# AUAV-X1_POWER_R1.net
KiCad netlist of a schematic drawn in Altium Designer
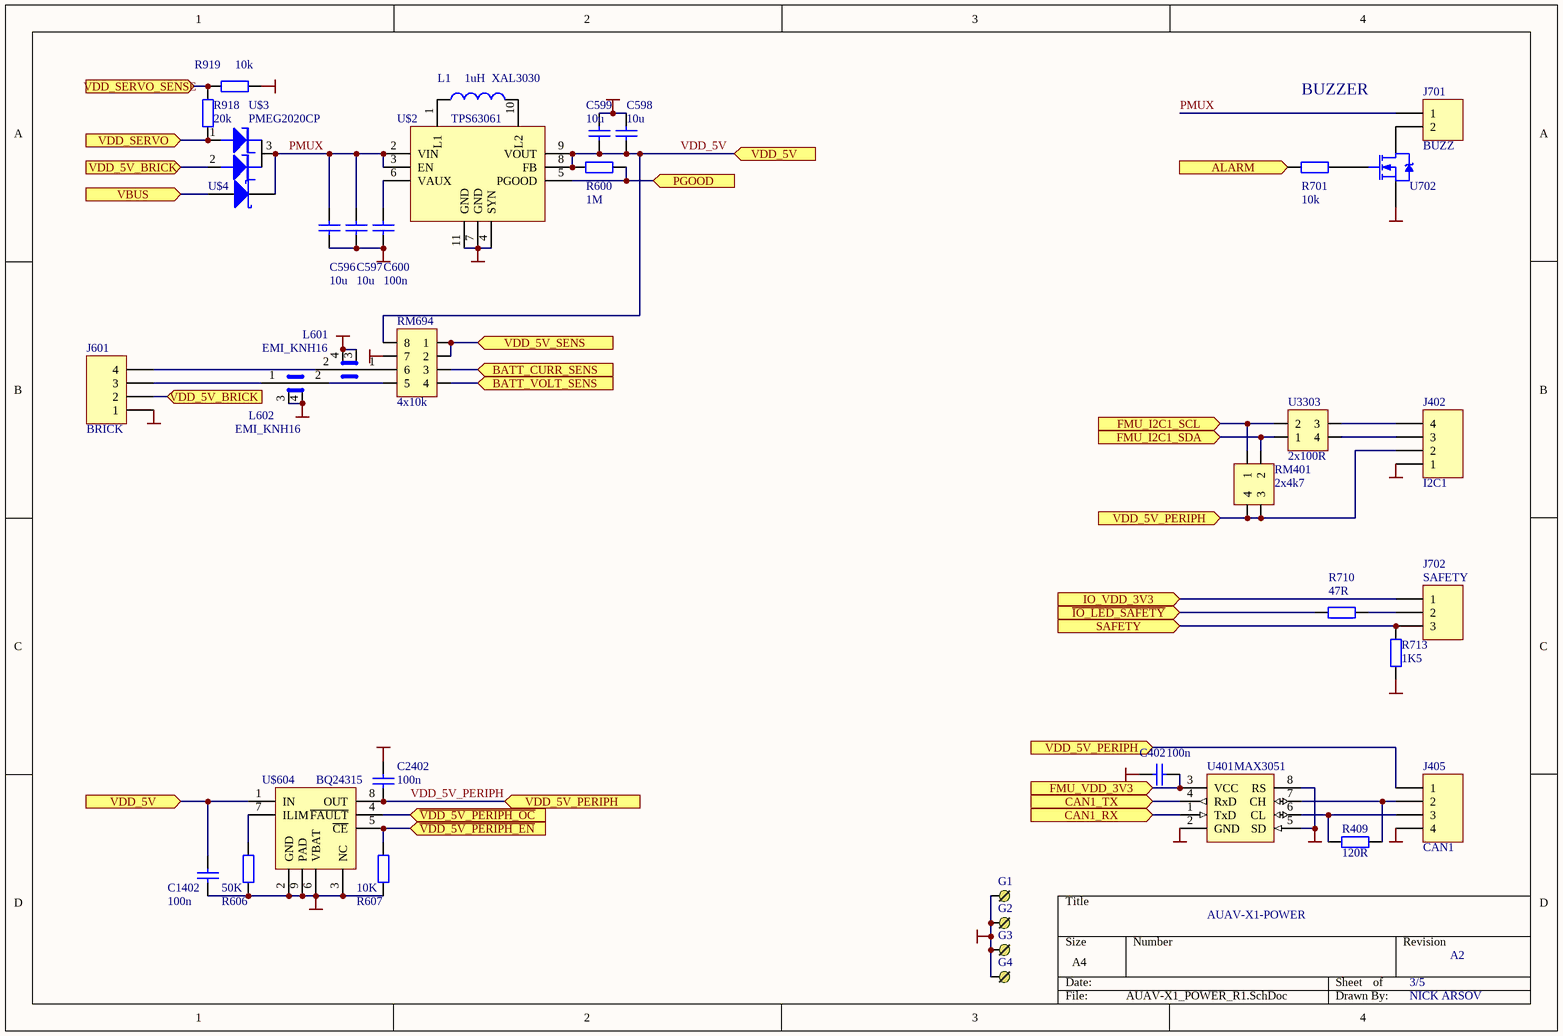
[diagram p0: AUAV-X1_POWER_R1.SchDoc]

(export (version "E")
  (design (tool "Eeschema 10.0.6"))
  (components
    (comp (ref "C402")
      (value "100n")
      (footprint "0402A")
      (description "Capacitor")
      (fields (field (name "PUBLISHER") "Altium Limited"))
      (libsource (lib "Miscellaneous Devices") (part "Cap"))
    )
    (comp (ref "C596")
      (value "10u")
      (footprint "0805A")
      (description "Capacitor")
      (fields (field (name "PUBLISHER") "Altium Limited"))
      (libsource (lib "Miscellaneous Devices") (part "Cap"))
    )
    (comp (ref "C597")
      (value "10u")
      (footprint "0805A")
      (description "Capacitor")
      (fields (field (name "PUBLISHER") "Altium Limited"))
      (libsource (lib "Miscellaneous Devices") (part "Cap"))
    )
    (comp (ref "C598")
      (value "10u")
      (footprint "0805A")
      (description "Capacitor")
      (fields (field (name "PUBLISHER") "Altium Limited"))
      (libsource (lib "Miscellaneous Devices") (part "Cap"))
    )
    (comp (ref "C599")
      (value "10u")
      (footprint "0805A")
      (description "Capacitor")
      (fields (field (name "PUBLISHER") "Altium Limited"))
      (libsource (lib "Miscellaneous Devices") (part "Cap"))
    )
    (comp (ref "C600")
      (value "100n")
      (footprint "0402A")
      (description "Capacitor")
      (fields (field (name "PUBLISHER") "Altium Limited"))
      (libsource (lib "Miscellaneous Devices") (part "Cap"))
    )
    (comp (ref "C1402")
      (value "100n")
      (footprint "0402A")
      (description "Capacitor")
      (fields (field (name "PUBLISHER") "Altium Limited"))
      (libsource (lib "Miscellaneous Devices") (part "Cap"))
    )
    (comp (ref "C2402")
      (value "100n")
      (footprint "0402A")
      (description "Capacitor")
      (fields (field (name "PUBLISHER") "Altium Limited"))
      (libsource (lib "Miscellaneous Devices") (part "Cap"))
    )
    (comp (ref "G1") (value "PLUG") (footprint "SMT_PAD_ROUND") (libsource (lib "My_Altium") (part "PLUG")))
    (comp (ref "G2") (value "PLUG") (footprint "SMT_PAD_ROUND") (libsource (lib "My_Altium") (part "PLUG")))
    (comp (ref "G3") (value "PLUG") (footprint "SMT_PAD_ROUND") (libsource (lib "My_Altium") (part "PLUG")))
    (comp (ref "G4") (value "PLUG") (footprint "SMT_PAD_ROUND") (libsource (lib "My_Altium") (part "PLUG")))
    (comp (ref "J402")
      (value "I2C1")
      (footprint "HDR1X4")
      (description "Header, 4-Pin")
      (fields (field (name "PUBLISHER") "Altium Limited"))
      (libsource (lib "") (part "Header 4_2"))
    )
    (comp (ref "J405")
      (value "CAN1")
      (footprint "HDR1X4")
      (description "Header, 4-Pin")
      (fields (field (name "PUBLISHER") "Altium Limited"))
      (libsource (lib "Miscellaneous Connectors") (part "Header 4"))
    )
    (comp (ref "J601")
      (value "BRICK")
      (footprint "HDR1X4")
      (description "Header, 4-Pin")
      (fields (field (name "PUBLISHER") "Altium Limited"))
      (libsource (lib "") (part "Header 4_1"))
    )
    (comp (ref "J701")
      (value "BUZZ")
      (footprint "HDR1X2")
      (description "Header, 2-Pin")
      (fields (field (name "PUBLISHER") "Altium Limited"))
      (libsource (lib "Miscellaneous Connectors") (part "Header 2"))
    )
    (comp (ref "J702")
      (value "SAFETY")
      (footprint "HDR1X3")
      (description "Header, 3-Pin")
      (fields (field (name "PUBLISHER") "Altium Limited"))
      (libsource (lib "Miscellaneous Connectors") (part "Header 3"))
    )
    (comp (ref "L1")
      (value "XAL3030")
      (footprint "XAL4040")
      (description "Inductor")
      (fields (field (name "ALTIUM_VALUE") "1uH") (field (name "PUBLISHER") "Altium Limited"))
      (libsource (lib "Miscellaneous Devices") (part "Inductor"))
    )
    (comp (ref "L601")
      (value "EMI_KNH16")
      (footprint "EMI_KNH16_0603")
      (libsource (lib "My_Altium") (part "EMI_KNH10"))
    )
    (comp (ref "L602")
      (value "EMI_KNH16")
      (footprint "EMI_KNH16_0603")
      (libsource (lib "My_Altium") (part "EMI_KNH10"))
    )
    (comp (ref "R409")
      (value "120R")
      (footprint "0603A")
      (description "Resistor")
      (fields (field (name "PUBLISHER") "Altium Limited"))
      (libsource (lib "Miscellaneous Devices") (part "Res2"))
    )
    (comp (ref "R600")
      (value "1M")
      (footprint "0402A")
      (description "Resistor")
      (fields (field (name "PUBLISHER") "Altium Limited"))
      (libsource (lib "") (part "Res2_2"))
    )
    (comp (ref "R606")
      (value "50K")
      (footprint "0402A")
      (description "Resistor")
      (fields (field (name "PUBLISHER") "Altium Limited"))
      (libsource (lib "") (part "Res2_1"))
    )
    (comp (ref "R607")
      (value "10K")
      (footprint "0402A")
      (description "Resistor")
      (fields (field (name "PUBLISHER") "Altium Limited"))
      (libsource (lib "") (part "Res2_1"))
    )
    (comp (ref "R701")
      (value "10k")
      (footprint "0402A")
      (description "Resistor")
      (fields (field (name "PUBLISHER") "Altium Limited"))
      (libsource (lib "") (part "Res2_2"))
    )
    (comp (ref "R710")
      (value "47R")
      (footprint "0402A")
      (description "Resistor")
      (fields (field (name "PUBLISHER") "Altium Limited"))
      (libsource (lib "Miscellaneous Devices") (part "Res2"))
    )
    (comp (ref "R713")
      (value "1K5")
      (footprint "0402A")
      (description "Resistor")
      (fields (field (name "PUBLISHER") "Altium Limited"))
      (libsource (lib "") (part "Res2_3"))
    )
    (comp (ref "R918")
      (value "20k")
      (footprint "0402A")
      (description "Resistor")
      (fields (field (name "PUBLISHER") "Altium Limited"))
      (libsource (lib "") (part "Res2_3"))
    )
    (comp (ref "R919")
      (value "10k")
      (footprint "0402A")
      (description "Resistor")
      (fields (field (name "PUBLISHER") "Altium Limited"))
      (libsource (lib "") (part "Res2_2"))
    )
    (comp (ref "RM401") (value "2x4k7") (footprint "RM2_0804") (libsource (lib "") (part "RES_SMD_2_1")))
    (comp (ref "RM694")
      (value "4x10k")
      (footprint "RM4_0804")
      (libsource (lib "My_Altium") (part "RES_SMD_4"))
    )
    (comp (ref "U$2")
      (value "TPS63061")
      (footprint "TPS63061")
      (libsource (lib "My_Altium") (part "TPS63061"))
    )
    (comp (ref "U$3")
      (value "PMEG2020CP")
      (footprint "pmeg2020cp")
      (libsource (lib "My_Altium") (part "PMEG2020CP"))
    )
    (comp (ref "U$4")
      (value "D Schottky")
      (footprint "SOD323F")
      (description "Schottky Diode")
      (fields (field (name "PUBLISHER") "Altium Limited"))
      (libsource (lib "Miscellaneous Devices") (part "D Schottky"))
    )
    (comp (ref "U$604")
      (value "BQ24315")
      (footprint "BQ24315")
      (libsource (lib "My_Altium") (part "BQ24315"))
    )
    (comp (ref "U401")
      (value "MAX3051")
      (footprint "SOT-23-8")
      (libsource (lib "My_Altium") (part "MAX3051"))
    )
    (comp (ref "U702")
      (value "ZXMN2F34MA")
      (footprint "2N7002-SOT323")
      (description "N-Channel Power MOSFET")
      (fields (field (name "PUBLISHER") "Altium Limited"))
      (libsource (lib "Miscellaneous Devices") (part "NMOS-2"))
    )
    (comp (ref "U3303")
      (value "2x100R")
      (footprint "RM2_0804")
      (libsource (lib "My_Altium") (part "RES_SMD_2"))
    )
  )
  (nets
    (net (code "1") (name "/ALARM") (class "Default")
      (node (ref "R701") (pin "1") (pinfunction "1_1") (pintype "passive"))
    )
    (net (code "2") (name "/BATT_CURR_SENS") (class "Default")
      (node (ref "RM694") (pin "3") (pinfunction "3_3") (pintype "passive"))
    )
    (net (code "3") (name "/BATT_VOLT_SENS") (class "Default")
      (node (ref "RM694") (pin "4") (pinfunction "4_4") (pintype "passive"))
    )
    (net (code "4") (name "/CAN1_RX") (class "Default")
      (node (ref "U401") (pin "1") (pinfunction "TxD_1") (pintype "input"))
    )
    (net (code "5") (name "/CAN1_TX") (class "Default")
      (node (ref "U401") (pin "4") (pinfunction "RxD_4") (pintype "output"))
    )
    (net (code "6") (name "/FMU_I2C1_SCL") (class "Default")
      (node (ref "RM401") (pin "1") (pinfunction "1_1") (pintype "passive"))
      (node (ref "U3303") (pin "2") (pinfunction "2_2") (pintype "passive"))
    )
    (net (code "7") (name "/FMU_I2C1_SDA") (class "Default")
      (node (ref "RM401") (pin "2") (pinfunction "2_2") (pintype "passive"))
      (node (ref "U3303") (pin "1") (pinfunction "1_1") (pintype "passive"))
    )
    (net (code "8") (name "/FMU_VDD_3V3") (class "Default")
      (node (ref "C402") (pin "2") (pinfunction "2_2") (pintype "passive"))
      (node (ref "U401") (pin "3") (pinfunction "VCC_3") (pintype "power_in"))
    )
    (net (code "9") (name "/IO_VDD_3V3") (class "Default")
      (node (ref "J702") (pin "1") (pinfunction "1_1") (pintype "passive"))
    )
    (net (code "10") (name "/PGOOD") (class "Default")
      (node (ref "R600") (pin "2") (pinfunction "2_2") (pintype "passive"))
      (node (ref "U$2") (pin "5") (pinfunction "PGOOD_5") (pintype "passive"))
    )
    (net (code "11") (name "/PMUX") (class "Default")
      (node (ref "C596") (pin "2") (pinfunction "2_2") (pintype "passive"))
      (node (ref "C597") (pin "2") (pinfunction "2_2") (pintype "passive"))
      (node (ref "J701") (pin "1") (pinfunction "1_1") (pintype "passive"))
      (node (ref "U$2") (pin "2") (pinfunction "VIN_2") (pintype "passive"))
      (node (ref "U$2") (pin "3") (pinfunction "EN_3") (pintype "passive"))
      (node (ref "U$3") (pin "3") (pintype "passive"))
      (node (ref "U$4") (pin "2") (pinfunction "K_2") (pintype "passive"))
    )
    (net (code "12") (name "/SAFETY") (class "Default")
      (node (ref "J702") (pin "3") (pinfunction "3_3") (pintype "passive"))
      (node (ref "R713") (pin "1") (pinfunction "1_1") (pintype "passive"))
    )
    (net (code "13") (name "/VBUS") (class "Default")
      (node (ref "U$4") (pin "1") (pinfunction "A_1") (pintype "passive"))
    )
    (net (code "14") (name "/VDD_5V") (class "Default")
      (node (ref "C1402") (pin "2") (pinfunction "2_2") (pintype "passive"))
      (node (ref "C598") (pin "2") (pinfunction "2_2") (pintype "passive"))
      (node (ref "C599") (pin "2") (pinfunction "2_2") (pintype "passive"))
      (node (ref "R600") (pin "1") (pinfunction "1_1") (pintype "passive"))
      (node (ref "RM694") (pin "8") (pinfunction "8_8") (pintype "passive"))
      (node (ref "U$2") (pin "8") (pinfunction "FB_8") (pintype "passive"))
      (node (ref "U$2") (pin "9") (pinfunction "VOUT_9") (pintype "passive"))
      (node (ref "U$604") (pin "1") (pinfunction "IN_1") (pintype "power_in"))
    )
    (net (code "15") (name "/VDD_5V_BRICK") (class "Default")
      (node (ref "J601") (pin "2") (pinfunction "2_2") (pintype "passive"))
      (node (ref "U$3") (pin "2") (pintype "passive"))
    )
    (net (code "16") (name "/VDD_5V_PERIPH") (class "Default")
      (node (ref "C2402") (pin "2") (pinfunction "2_2") (pintype "passive"))
      (node (ref "J402") (pin "2") (pinfunction "2_2") (pintype "passive"))
      (node (ref "J405") (pin "1") (pinfunction "1_1") (pintype "passive"))
      (node (ref "RM401") (pin "3") (pinfunction "3_3") (pintype "passive"))
      (node (ref "RM401") (pin "4") (pinfunction "4_4") (pintype "passive"))
      (node (ref "U$604") (pin "8") (pinfunction "OUT_8") (pintype "passive"))
    )
    (net (code "17") (name "/VDD_5V_SENS") (class "Default")
      (node (ref "RM694") (pin "1") (pinfunction "1_1") (pintype "passive"))
      (node (ref "RM694") (pin "2") (pinfunction "2_2") (pintype "passive"))
    )
    (net (code "18") (name "/VDD_SERVO") (class "Default")
      (node (ref "R918") (pin "2") (pinfunction "2_2") (pintype "passive"))
      (node (ref "U$3") (pin "1") (pintype "passive"))
    )
    (net (code "19") (name "/VDD_SERVO_SENSE") (class "Default")
      (node (ref "R918") (pin "1") (pinfunction "1_1") (pintype "passive"))
      (node (ref "R919") (pin "1") (pinfunction "1_1") (pintype "passive"))
    )
    (net (code "20") (name "/~{IO_LED_SAFETY}") (class "Default")
      (node (ref "R710") (pin "2") (pinfunction "2_2") (pintype "passive"))
    )
    (net (code "21") (name "/~{VDD_5V_PERIPH_EN}") (class "Default")
      (node (ref "R607") (pin "2") (pinfunction "2_2") (pintype "passive"))
      (node (ref "U$604") (pin "5") (pinfunction "~{CE}_5") (pintype "passive"))
    )
    (net (code "22") (name "/~{VDD_5V_PERIPH_OC}") (class "Default")
      (node (ref "U$604") (pin "4") (pinfunction "~{FAULT}_4") (pintype "passive"))
    )
    (net (code "23") (name "GND") (class "Default")
      (node (ref "C1402") (pin "1") (pinfunction "1_1") (pintype "passive"))
      (node (ref "C2402") (pin "1") (pinfunction "1_1") (pintype "passive"))
      (node (ref "C402") (pin "1") (pinfunction "1_1") (pintype "passive"))
      (node (ref "C596") (pin "1") (pinfunction "1_1") (pintype "passive"))
      (node (ref "C597") (pin "1") (pinfunction "1_1") (pintype "passive"))
      (node (ref "C598") (pin "1") (pinfunction "1_1") (pintype "passive"))
      (node (ref "C599") (pin "1") (pinfunction "1_1") (pintype "passive"))
      (node (ref "C600") (pin "1") (pinfunction "1_1") (pintype "passive"))
      (node (ref "G1") (pin "1") (pintype "passive"))
      (node (ref "G2") (pin "1") (pintype "passive"))
      (node (ref "G3") (pin "1") (pintype "passive"))
      (node (ref "G4") (pin "1") (pintype "passive"))
      (node (ref "J402") (pin "1") (pinfunction "1_1") (pintype "passive"))
      (node (ref "J405") (pin "4") (pinfunction "4_4") (pintype "passive"))
      (node (ref "J601") (pin "1") (pinfunction "1_1") (pintype "passive"))
      (node (ref "L601") (pin "3") (pinfunction "G_3") (pintype "power_in"))
      (node (ref "L601") (pin "4") (pinfunction "G_4") (pintype "passive"))
      (node (ref "L602") (pin "3") (pinfunction "G_3") (pintype "power_in"))
      (node (ref "L602") (pin "4") (pinfunction "G_4") (pintype "passive"))
      (node (ref "R606") (pin "1") (pinfunction "1_1") (pintype "passive"))
      (node (ref "R607") (pin "1") (pinfunction "1_1") (pintype "passive"))
      (node (ref "R713") (pin "2") (pinfunction "2_2") (pintype "passive"))
      (node (ref "R919") (pin "2") (pinfunction "2_2") (pintype "passive"))
      (node (ref "RM694") (pin "7") (pinfunction "7_7") (pintype "passive"))
      (node (ref "U$2") (pin "11") (pinfunction "GND_11") (pintype "passive"))
      (node (ref "U$2") (pin "4") (pinfunction "SYN_4") (pintype "passive"))
      (node (ref "U$2") (pin "7") (pinfunction "GND_7") (pintype "passive"))
      (node (ref "U$604") (pin "2") (pinfunction "GND_2") (pintype "passive"))
      (node (ref "U$604") (pin "3") (pinfunction "NC_3") (pintype "passive"))
      (node (ref "U$604") (pin "6") (pinfunction "VBAT_6") (pintype "passive"))
      (node (ref "U$604") (pin "9") (pinfunction "PAD_9") (pintype "passive"))
      (node (ref "U401") (pin "2") (pinfunction "GND_2") (pintype "power_in"))
      (node (ref "U401") (pin "5") (pinfunction "SD_5") (pintype "input"))
      (node (ref "U401") (pin "8") (pinfunction "RS_8") (pintype "passive"))
      (node (ref "U702") (pin "2") (pinfunction "S_2") (pintype "passive"))
    )
    (net (code "24") (name "Net-(J402-Pad3)") (class "Default")
      (node (ref "J402") (pin "3") (pinfunction "3_3") (pintype "passive"))
      (node (ref "U3303") (pin "4") (pinfunction "4_4") (pintype "passive"))
    )
    (net (code "25") (name "Net-(J402-Pad4)") (class "Default")
      (node (ref "J402") (pin "4") (pinfunction "4_4") (pintype "passive"))
      (node (ref "U3303") (pin "3") (pinfunction "3_3") (pintype "passive"))
    )
    (net (code "26") (name "Net-(J702-Pad2)") (class "Default")
      (node (ref "J702") (pin "2") (pinfunction "2_2") (pintype "passive"))
      (node (ref "R710") (pin "1") (pinfunction "1_1") (pintype "passive"))
    )
    (net (code "27") (name "Net-(L601-L1)") (class "Default")
      (node (ref "L601") (pin "1") (pinfunction "L1_1") (pintype "passive"))
      (node (ref "RM694") (pin "6") (pinfunction "6_6") (pintype "passive"))
    )
    (net (code "28") (name "Net-(L601-L2)") (class "Default")
      (node (ref "J601") (pin "4") (pinfunction "4_4") (pintype "passive"))
      (node (ref "L601") (pin "2") (pinfunction "L2_2") (pintype "passive"))
    )
    (net (code "29") (name "Net-(L602-L1)") (class "Default")
      (node (ref "J601") (pin "3") (pinfunction "3_3") (pintype "passive"))
      (node (ref "L602") (pin "1") (pinfunction "L1_1") (pintype "passive"))
    )
    (net (code "30") (name "Net-(L602-L2)") (class "Default")
      (node (ref "L602") (pin "2") (pinfunction "L2_2") (pintype "passive"))
      (node (ref "RM694") (pin "5") (pinfunction "5_5") (pintype "passive"))
    )
    (net (code "31") (name "Net-(U$2-L1)") (class "Default")
      (node (ref "L1") (pin "1") (pinfunction "1_1") (pintype "passive"))
      (node (ref "U$2") (pin "1") (pinfunction "L1_1") (pintype "passive"))
    )
    (net (code "32") (name "Net-(U$2-L2)") (class "Default")
      (node (ref "L1") (pin "2") (pinfunction "2_2") (pintype "passive"))
      (node (ref "U$2") (pin "10") (pinfunction "L2_10") (pintype "passive"))
    )
    (net (code "33") (name "Net-(U$2-VAUX)") (class "Default")
      (node (ref "C600") (pin "2") (pinfunction "2_2") (pintype "passive"))
      (node (ref "U$2") (pin "6") (pinfunction "VAUX_6") (pintype "passive"))
    )
    (net (code "34") (name "Net-(U$604-ILIM)") (class "Default")
      (node (ref "R606") (pin "2") (pinfunction "2_2") (pintype "passive"))
      (node (ref "U$604") (pin "7") (pinfunction "ILIM_7") (pintype "passive"))
    )
    (net (code "35") (name "Net-(U401-CH)") (class "Default")
      (node (ref "J405") (pin "2") (pinfunction "2_2") (pintype "passive"))
      (node (ref "R409") (pin "1") (pinfunction "1_1") (pintype "passive"))
      (node (ref "U401") (pin "7") (pinfunction "CH_7") (pintype "bidirectional"))
    )
    (net (code "36") (name "Net-(U401-CL)") (class "Default")
      (node (ref "J405") (pin "3") (pinfunction "3_3") (pintype "passive"))
      (node (ref "R409") (pin "2") (pinfunction "2_2") (pintype "passive"))
      (node (ref "U401") (pin "6") (pinfunction "CL_6") (pintype "bidirectional"))
    )
    (net (code "37") (name "Net-(U702-D)") (class "Default")
      (node (ref "J701") (pin "2") (pinfunction "2_2") (pintype "passive"))
      (node (ref "U702") (pin "1") (pinfunction "D_1") (pintype "passive"))
    )
    (net (code "38") (name "Net-(U702-G)") (class "Default")
      (node (ref "R701") (pin "2") (pinfunction "2_2") (pintype "passive"))
      (node (ref "U702") (pin "3") (pinfunction "G_3") (pintype "passive"))
    )
  )
)
